# Display_Key_Eye.net
KiCad netlist of a schematic drawn in Altium Designer
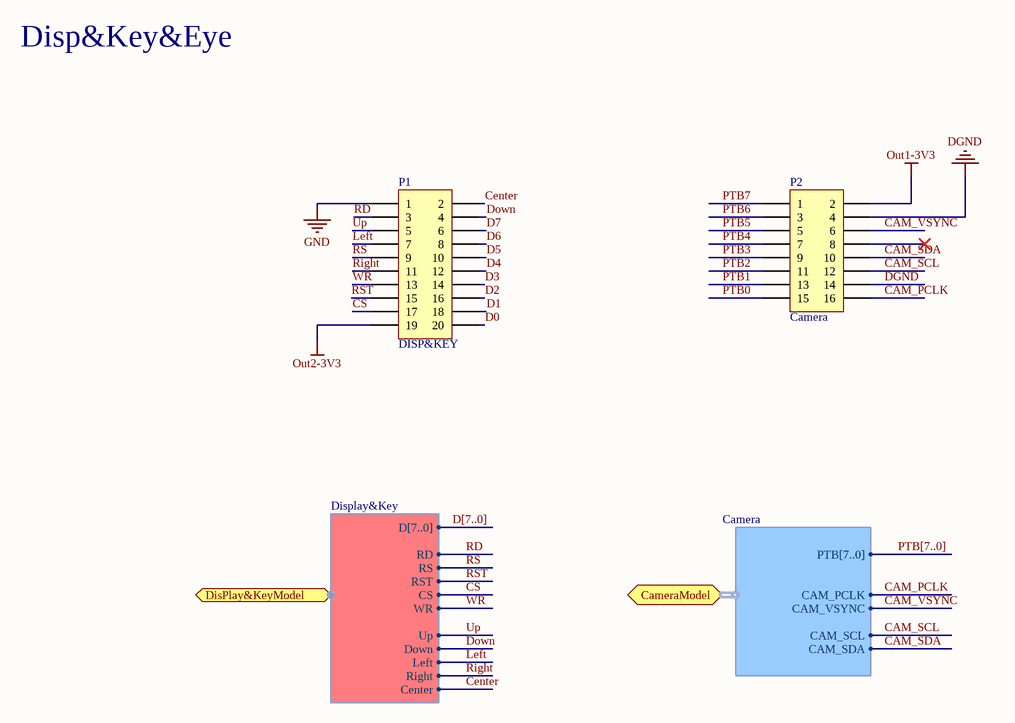
[diagram p0: Display&Key&Eye.SchDoc]

(export (version "E")
  (design (tool "Eeschema 10.0.6"))
  (components
    (comp (ref "P1")
      (value "DISP&KEY")
      (footprint "HDR2X10")
      (description "Header, 10-Pin, Dual row")
      (fields (field (name "PUBLISHER") "Altium Limited"))
      (libsource (lib "Miscellaneous Connectors") (part "Header 10X2"))
    )
    (comp (ref "P2")
      (value "Camera")
      (footprint "HDR2X8")
      (description "Header, 8-Pin, Dual row")
      (fields (field (name "PUBLISHER") "Altium Limited"))
      (libsource (lib "Miscellaneous Connectors") (part "Header 8X2"))
    )
  )
  (nets
    (net (code "3") (name "/CAM_PCLK") (class "Default")
      (node (ref "P2") (pin "16") (pinfunction "16_16") (pintype "passive"))
    )
    (net (code "4") (name "/CAM_SCL") (class "Default")
      (node (ref "P2") (pin "12") (pinfunction "12_12") (pintype "passive"))
    )
    (net (code "5") (name "/CAM_SDA") (class "Default")
      (node (ref "P2") (pin "10") (pinfunction "10_10") (pintype "passive"))
    )
    (net (code "6") (name "/CAM_VSYNC") (class "Default")
      (node (ref "P2") (pin "6") (pinfunction "6_6") (pintype "passive"))
    )
    (net (code "7") (name "/CS") (class "Default")
      (node (ref "P1") (pin "17") (pinfunction "17_17") (pintype "passive"))
    )
    (net (code "9") (name "/Center") (class "Default")
      (node (ref "P1") (pin "2") (pinfunction "2_2") (pintype "passive"))
    )
    (net (code "10") (name "/D0") (class "Default")
      (node (ref "P1") (pin "20") (pinfunction "20_20") (pintype "passive"))
    )
    (net (code "11") (name "/D1") (class "Default")
      (node (ref "P1") (pin "18") (pinfunction "18_18") (pintype "passive"))
    )
    (net (code "12") (name "/D2") (class "Default")
      (node (ref "P1") (pin "16") (pinfunction "16_16") (pintype "passive"))
    )
    (net (code "13") (name "/D3") (class "Default")
      (node (ref "P1") (pin "14") (pinfunction "14_14") (pintype "passive"))
    )
    (net (code "14") (name "/D4") (class "Default")
      (node (ref "P1") (pin "12") (pinfunction "12_12") (pintype "passive"))
    )
    (net (code "15") (name "/D5") (class "Default")
      (node (ref "P1") (pin "10") (pinfunction "10_10") (pintype "passive"))
    )
    (net (code "16") (name "/D6") (class "Default")
      (node (ref "P1") (pin "8") (pinfunction "8_8") (pintype "passive"))
    )
    (net (code "17") (name "/D7") (class "Default")
      (node (ref "P1") (pin "6") (pinfunction "6_6") (pintype "passive"))
    )
    (net (code "19") (name "/Down") (class "Default")
      (node (ref "P1") (pin "4") (pinfunction "4_4") (pintype "passive"))
    )
    (net (code "20") (name "/Left") (class "Default")
      (node (ref "P1") (pin "7") (pinfunction "7_7") (pintype "passive"))
    )
    (net (code "21") (name "/PTB0") (class "Default")
      (node (ref "P2") (pin "15") (pinfunction "15_15") (pintype "passive"))
    )
    (net (code "22") (name "/PTB1") (class "Default")
      (node (ref "P2") (pin "13") (pinfunction "13_13") (pintype "passive"))
    )
    (net (code "23") (name "/PTB2") (class "Default")
      (node (ref "P2") (pin "11") (pinfunction "11_11") (pintype "passive"))
    )
    (net (code "24") (name "/PTB3") (class "Default")
      (node (ref "P2") (pin "9") (pinfunction "9_9") (pintype "passive"))
    )
    (net (code "25") (name "/PTB4") (class "Default")
      (node (ref "P2") (pin "7") (pinfunction "7_7") (pintype "passive"))
    )
    (net (code "26") (name "/PTB5") (class "Default")
      (node (ref "P2") (pin "5") (pinfunction "5_5") (pintype "passive"))
    )
    (net (code "27") (name "/PTB6") (class "Default")
      (node (ref "P2") (pin "3") (pinfunction "3_3") (pintype "passive"))
    )
    (net (code "28") (name "/PTB7") (class "Default")
      (node (ref "P2") (pin "1") (pinfunction "1_1") (pintype "passive"))
    )
    (net (code "29") (name "/RD") (class "Default")
      (node (ref "P1") (pin "3") (pinfunction "3_3") (pintype "passive"))
    )
    (net (code "30") (name "/RST") (class "Default")
      (node (ref "P1") (pin "15") (pinfunction "15_15") (pintype "passive"))
    )
    (net (code "31") (name "/Right") (class "Default")
      (node (ref "P1") (pin "11") (pinfunction "11_11") (pintype "passive"))
    )
    (net (code "32") (name "/Up") (class "Default")
      (node (ref "P1") (pin "5") (pinfunction "5_5") (pintype "passive"))
    )
    (net (code "33") (name "/WR") (class "Default")
      (node (ref "P1") (pin "13") (pinfunction "13_13") (pintype "passive"))
    )
    (net (code "36") (name "/~{RS}") (class "Default")
      (node (ref "P1") (pin "9") (pinfunction "9_9") (pintype "passive"))
    )
    (net (code "37") (name "DGND") (class "Default")
      (node (ref "P2") (pin "14") (pinfunction "14_14") (pintype "passive"))
      (node (ref "P2") (pin "4") (pinfunction "4_4") (pintype "passive"))
    )
    (net (code "38") (name "GND") (class "Default")
      (node (ref "P1") (pin "1") (pinfunction "1_1") (pintype "passive"))
    )
    (net (code "39") (name "Out1-3V3") (class "Default")
      (node (ref "P2") (pin "2") (pinfunction "2_2") (pintype "passive"))
    )
    (net (code "40") (name "Out2-3V3") (class "Default")
      (node (ref "P1") (pin "19") (pinfunction "19_19") (pintype "passive"))
    )
    (net (code "41") (name "unconnected-(P2-Pad8)") (class "Default")
      (node (ref "P2") (pin "8") (pinfunction "8_8") (pintype "passive+no_connect"))
    )
  )
)
